# ant_esc_schematic.net
KiCad netlist of a schematic drawn in EAGLE
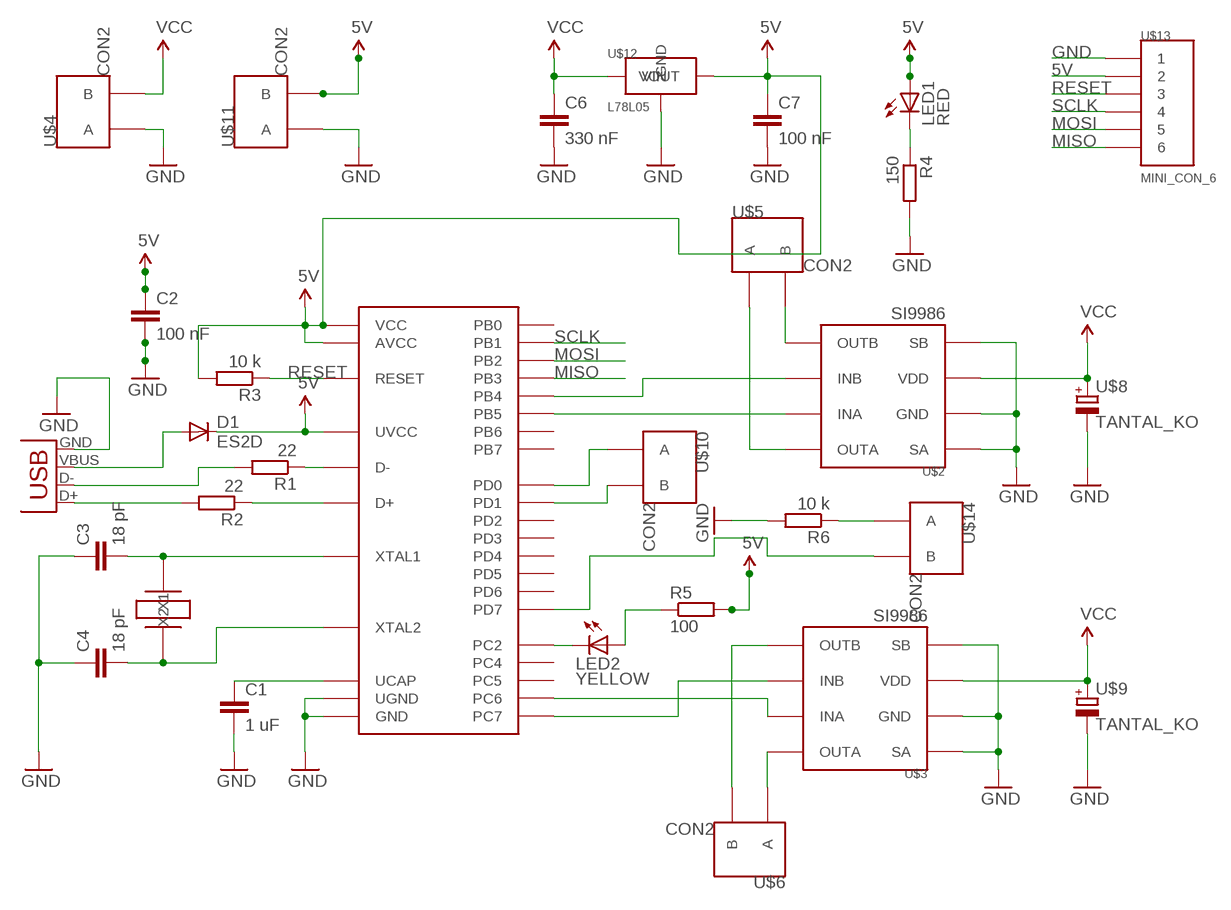
[diagram p0: schematic, sheet 1]

(export (version "E")
  (design (tool "Eeschema 10.0.6"))
  (components
    (comp (ref "C1")
      (value "1 uF")
      (footprint "eagle-import:C0805")
      (libsource (lib "eagle-import") (part "C-EUC0805"))
    )
    (comp (ref "C2")
      (value "100 nF")
      (footprint "eagle-import:C0805")
      (libsource (lib "eagle-import") (part "C-EUC0805"))
    )
    (comp (ref "C3")
      (value "18 pF")
      (footprint "eagle-import:C0805")
      (libsource (lib "eagle-import") (part "C-EUC0805"))
    )
    (comp (ref "C4")
      (value "18 pF")
      (footprint "eagle-import:C0805")
      (libsource (lib "eagle-import") (part "C-EUC0805"))
    )
    (comp (ref "C6")
      (value "330 nF")
      (footprint "eagle-import:C0805")
      (libsource (lib "eagle-import") (part "C-EUC0805"))
    )
    (comp (ref "C7")
      (value "100 nF")
      (footprint "eagle-import:C0805")
      (libsource (lib "eagle-import") (part "C-EUC0805"))
    )
    (comp (ref "D1")
      (value "ES2D")
      (footprint "eagle-import:SMB")
      (libsource (lib "eagle-import") (part "ES2D"))
    )
    (comp (ref "JP1")
      (value "USBSMD")
      (footprint "eagle-import:USB-MINIB")
      (libsource (lib "eagle-import") (part "USBSMD"))
    )
    (comp (ref "LED1")
      (value "RED")
      (footprint "eagle-import:CHIPLED_0805")
      (libsource (lib "eagle-import") (part "LEDCHIPLED_0805"))
    )
    (comp (ref "LED2")
      (value "YELLOW")
      (footprint "eagle-import:CHIPLED_0805")
      (libsource (lib "eagle-import") (part "LEDCHIPLED_0805"))
    )
    (comp (ref "R1")
      (value "22")
      (footprint "eagle-import:M0805")
      (libsource (lib "eagle-import") (part "R-EU_M0805"))
    )
    (comp (ref "R2")
      (value "22")
      (footprint "eagle-import:M0805")
      (libsource (lib "eagle-import") (part "R-EU_M0805"))
    )
    (comp (ref "R3")
      (value "10 k")
      (footprint "eagle-import:M0805")
      (libsource (lib "eagle-import") (part "R-EU_M0805"))
    )
    (comp (ref "R4")
      (value "150")
      (footprint "eagle-import:M0805")
      (libsource (lib "eagle-import") (part "R-EU_M0805"))
    )
    (comp (ref "R5")
      (value "100")
      (footprint "eagle-import:M0805")
      (libsource (lib "eagle-import") (part "R-EU_M0805"))
    )
    (comp (ref "R6")
      (value "10 k")
      (footprint "eagle-import:M0805")
      (libsource (lib "eagle-import") (part "R-EU_M0805"))
    )
    (comp (ref "U$1")
      (value "ATMEGA8U2")
      (footprint "eagle-import:TQFP32-08")
      (libsource (lib "eagle-import") (part "ATMEGA8U2"))
    )
    (comp (ref "U$2")
      (value "SI9986")
      (footprint "eagle-import:SOIC8")
      (libsource (lib "eagle-import") (part "SI9986"))
    )
    (comp (ref "U$3")
      (value "SI9986")
      (footprint "eagle-import:SOIC8")
      (libsource (lib "eagle-import") (part "SI9986"))
    )
    (comp (ref "U$4")
      (value "CON2")
      (footprint "eagle-import:332-02")
      (libsource (lib "eagle-import") (part "CON2"))
    )
    (comp (ref "U$5")
      (value "CON2")
      (footprint "eagle-import:332-02")
      (libsource (lib "eagle-import") (part "CON2"))
    )
    (comp (ref "U$6")
      (value "CON2")
      (footprint "eagle-import:332-02")
      (libsource (lib "eagle-import") (part "CON2"))
    )
    (comp (ref "U$7")
      (value "16 MHz")
      (footprint "eagle-import:ABM3")
      (libsource (lib "eagle-import") (part "XTAL_16MHZ_ABM3"))
    )
    (comp (ref "U$8")
      (value "TANTAL_KO")
      (footprint "eagle-import:KEMET_C")
      (libsource (lib "eagle-import") (part "TANTAL_KO"))
    )
    (comp (ref "U$9")
      (value "TANTAL_KO")
      (footprint "eagle-import:KEMET_C")
      (libsource (lib "eagle-import") (part "TANTAL_KO"))
    )
    (comp (ref "U$10")
      (value "CON2")
      (footprint "eagle-import:332-02")
      (libsource (lib "eagle-import") (part "CON2"))
    )
    (comp (ref "U$11")
      (value "CON2")
      (footprint "eagle-import:332-02")
      (libsource (lib "eagle-import") (part "CON2"))
    )
    (comp (ref "U$12")
      (value "L78L05")
      (footprint "eagle-import:SOT89")
      (libsource (lib "eagle-import") (part "L78L05"))
    )
    (comp (ref "U$13")
      (value "MINI_CON_6")
      (footprint "eagle-import:MIN_CON_6")
      (libsource (lib "eagle-import") (part "MINI_CON_6"))
    )
    (comp (ref "U$14")
      (value "CON2")
      (footprint "eagle-import:332-02")
      (libsource (lib "eagle-import") (part "CON2"))
    )
  )
  (nets
    (net (code "1") (name "/MISO") (class "Default")
      (node (ref "U$1") (pin "PB3") (pinfunction "PB3_PB3") (pintype "bidirectional"))
      (node (ref "U$13") (pin "6") (pinfunction "6_6") (pintype "bidirectional"))
    )
    (net (code "2") (name "/MOSI") (class "Default")
      (node (ref "U$1") (pin "PB2") (pinfunction "PB2_PB2") (pintype "bidirectional"))
      (node (ref "U$13") (pin "5") (pinfunction "5_5") (pintype "bidirectional"))
    )
    (net (code "3") (name "/RESET") (class "Default")
      (node (ref "R3") (pin "1") (pinfunction "1_1") (pintype "passive"))
      (node (ref "U$1") (pin "RESET") (pinfunction "RESET_RESET") (pintype "bidirectional"))
      (node (ref "U$13") (pin "3") (pinfunction "3_3") (pintype "bidirectional"))
    )
    (net (code "4") (name "/SCLK") (class "Default")
      (node (ref "U$1") (pin "PB1") (pinfunction "PB1_PB1") (pintype "bidirectional"))
      (node (ref "U$13") (pin "4") (pinfunction "4_4") (pintype "bidirectional"))
    )
    (net (code "5") (name "5V") (class "Default")
      (node (ref "C2") (pin "1") (pinfunction "1_1") (pintype "passive"))
      (node (ref "C7") (pin "1") (pinfunction "1_1") (pintype "passive"))
      (node (ref "D1") (pin "C") (pinfunction "C_C") (pintype "passive"))
      (node (ref "LED1") (pin "A") (pinfunction "A_A") (pintype "passive"))
      (node (ref "R3") (pin "2") (pinfunction "2_2") (pintype "passive"))
      (node (ref "R5") (pin "2") (pinfunction "2_2") (pintype "passive"))
      (node (ref "U$1") (pin "AVCC") (pinfunction "AVCC_AVCC") (pintype "bidirectional"))
      (node (ref "U$1") (pin "UVCC") (pinfunction "UVCC_UVCC") (pintype "bidirectional"))
      (node (ref "U$1") (pin "VCC") (pinfunction "VCC_VCC") (pintype "bidirectional"))
      (node (ref "U$11") (pin "2") (pinfunction "B_2") (pintype "bidirectional"))
      (node (ref "U$12") (pin "VOUT") (pinfunction "VOUT_VOUT") (pintype "bidirectional"))
      (node (ref "U$13") (pin "2") (pinfunction "2_2") (pintype "bidirectional"))
    )
    (net (code "6") (name "GND") (class "Default")
      (node (ref "C1") (pin "2") (pinfunction "2_2") (pintype "passive"))
      (node (ref "C2") (pin "2") (pinfunction "2_2") (pintype "passive"))
      (node (ref "C3") (pin "1") (pinfunction "1_1") (pintype "passive"))
      (node (ref "C4") (pin "1") (pinfunction "1_1") (pintype "passive"))
      (node (ref "C6") (pin "2") (pinfunction "2_2") (pintype "passive"))
      (node (ref "C7") (pin "2") (pinfunction "2_2") (pintype "passive"))
      (node (ref "JP1") (pin "GND") (pinfunction "GND_GND") (pintype "bidirectional"))
      (node (ref "R4") (pin "2") (pinfunction "2_2") (pintype "passive"))
      (node (ref "R6") (pin "2") (pinfunction "2_2") (pintype "passive"))
      (node (ref "U$1") (pin "GND") (pinfunction "GND_GND") (pintype "bidirectional"))
      (node (ref "U$1") (pin "UGND") (pinfunction "UGND_UGND") (pintype "bidirectional"))
      (node (ref "U$11") (pin "1") (pinfunction "A_1") (pintype "bidirectional"))
      (node (ref "U$12") (pin "2@1") (pinfunction "GND_2@1") (pintype "bidirectional"))
      (node (ref "U$12") (pin "GND") (pinfunction "GND_GND") (pintype "bidirectional"))
      (node (ref "U$13") (pin "1") (pinfunction "1_1") (pintype "bidirectional"))
      (node (ref "U$2") (pin "GND") (pinfunction "GND_GND") (pintype "bidirectional"))
      (node (ref "U$2") (pin "SA") (pinfunction "SA_SA") (pintype "bidirectional"))
      (node (ref "U$2") (pin "SB") (pinfunction "SB_SB") (pintype "bidirectional"))
      (node (ref "U$3") (pin "GND") (pinfunction "GND_GND") (pintype "bidirectional"))
      (node (ref "U$3") (pin "SA") (pinfunction "SA_SA") (pintype "bidirectional"))
      (node (ref "U$3") (pin "SB") (pinfunction "SB_SB") (pintype "bidirectional"))
      (node (ref "U$4") (pin "1") (pinfunction "A_1") (pintype "bidirectional"))
      (node (ref "U$8") (pin "CATHODE-") (pinfunction "-_CATHODE-") (pintype "passive"))
      (node (ref "U$9") (pin "CATHODE-") (pinfunction "-_CATHODE-") (pintype "passive"))
    )
    (net (code "7") (name "Net-(C1-Pad1)") (class "Default")
      (node (ref "C1") (pin "1") (pinfunction "1_1") (pintype "passive"))
      (node (ref "U$1") (pin "UCAP") (pinfunction "UCAP_UCAP") (pintype "bidirectional"))
    )
    (net (code "8") (name "Net-(C3-Pad2)") (class "Default")
      (node (ref "C3") (pin "2") (pinfunction "2_2") (pintype "passive"))
      (node (ref "U$1") (pin "XTAL1") (pinfunction "XTAL1_XTAL1") (pintype "bidirectional"))
      (node (ref "U$7") (pin "X2") (pinfunction "X2_X2") (pintype "bidirectional"))
    )
    (net (code "9") (name "Net-(C4-Pad2)") (class "Default")
      (node (ref "C4") (pin "2") (pinfunction "2_2") (pintype "passive"))
      (node (ref "U$1") (pin "XTAL2") (pinfunction "XTAL2_XTAL2") (pintype "bidirectional"))
      (node (ref "U$7") (pin "X1") (pinfunction "X1_X1") (pintype "bidirectional"))
    )
    (net (code "10") (name "Net-(D1-PadA)") (class "Default")
      (node (ref "D1") (pin "A") (pinfunction "A_A") (pintype "passive"))
      (node (ref "JP1") (pin "VBUS") (pinfunction "VBUS_VBUS") (pintype "bidirectional"))
    )
    (net (code "11") (name "Net-(JP1-PadD+)") (class "Default")
      (node (ref "JP1") (pin "D+") (pinfunction "D+_D+") (pintype "bidirectional"))
      (node (ref "R2") (pin "2") (pinfunction "2_2") (pintype "passive"))
    )
    (net (code "12") (name "Net-(JP1-PadD-)") (class "Default")
      (node (ref "JP1") (pin "D-") (pinfunction "D-_D-") (pintype "bidirectional"))
      (node (ref "R1") (pin "2") (pinfunction "2_2") (pintype "passive"))
    )
    (net (code "13") (name "Net-(LED1-PadC)") (class "Default")
      (node (ref "LED1") (pin "C") (pinfunction "C_C") (pintype "passive"))
      (node (ref "R4") (pin "1") (pinfunction "1_1") (pintype "passive"))
    )
    (net (code "14") (name "Net-(LED2-PadA)") (class "Default")
      (node (ref "LED2") (pin "A") (pinfunction "A_A") (pintype "passive"))
      (node (ref "R5") (pin "1") (pinfunction "1_1") (pintype "passive"))
    )
    (net (code "15") (name "Net-(LED2-PadC)") (class "Default")
      (node (ref "LED2") (pin "C") (pinfunction "C_C") (pintype "passive"))
      (node (ref "U$1") (pin "PC2") (pinfunction "PC2_PC2") (pintype "bidirectional"))
    )
    (net (code "16") (name "Net-(R1-Pad1)") (class "Default")
      (node (ref "R1") (pin "1") (pinfunction "1_1") (pintype "passive"))
      (node (ref "U$1") (pin "D-") (pinfunction "D-_D-") (pintype "bidirectional"))
    )
    (net (code "17") (name "Net-(R2-Pad1)") (class "Default")
      (node (ref "R2") (pin "1") (pinfunction "1_1") (pintype "passive"))
      (node (ref "U$1") (pin "D+") (pinfunction "D+_D+") (pintype "bidirectional"))
    )
    (net (code "18") (name "Net-(U$1-PadPB4)") (class "Default")
      (node (ref "U$1") (pin "PB4") (pinfunction "PB4_PB4") (pintype "bidirectional"))
      (node (ref "U$2") (pin "INB") (pinfunction "INB_INB") (pintype "bidirectional"))
    )
    (net (code "19") (name "Net-(U$1-PadPB5)") (class "Default")
      (node (ref "U$1") (pin "PB5") (pinfunction "PB5_PB5") (pintype "bidirectional"))
      (node (ref "U$2") (pin "INA") (pinfunction "INA_INA") (pintype "bidirectional"))
    )
    (net (code "20") (name "Net-(U$1-PadPC6)") (class "Default")
      (node (ref "U$1") (pin "PC6") (pinfunction "PC6_PC6") (pintype "bidirectional"))
      (node (ref "U$3") (pin "INA") (pinfunction "INA_INA") (pintype "bidirectional"))
    )
    (net (code "21") (name "Net-(U$1-PadPC7)") (class "Default")
      (node (ref "U$1") (pin "PC7") (pinfunction "PC7_PC7") (pintype "bidirectional"))
      (node (ref "U$3") (pin "INB") (pinfunction "INB_INB") (pintype "bidirectional"))
    )
    (net (code "22") (name "Net-(U$5-A)") (class "Default")
      (node (ref "U$2") (pin "OUTA") (pinfunction "OUTA_OUTA") (pintype "bidirectional"))
      (node (ref "U$5") (pin "1") (pinfunction "A_1") (pintype "bidirectional"))
    )
    (net (code "23") (name "Net-(U$5-B)") (class "Default")
      (node (ref "U$2") (pin "OUTB") (pinfunction "OUTB_OUTB") (pintype "bidirectional"))
      (node (ref "U$5") (pin "2") (pinfunction "B_2") (pintype "bidirectional"))
    )
    (net (code "24") (name "Net-(U$6-A)") (class "Default")
      (node (ref "U$3") (pin "OUTA") (pinfunction "OUTA_OUTA") (pintype "bidirectional"))
      (node (ref "U$6") (pin "1") (pinfunction "A_1") (pintype "bidirectional"))
    )
    (net (code "25") (name "Net-(U$6-B)") (class "Default")
      (node (ref "U$3") (pin "OUTB") (pinfunction "OUTB_OUTB") (pintype "bidirectional"))
      (node (ref "U$6") (pin "2") (pinfunction "B_2") (pintype "bidirectional"))
    )
    (net (code "26") (name "Net-(U$10-A)") (class "Default")
      (node (ref "U$1") (pin "PD0") (pinfunction "PD0_PD0") (pintype "bidirectional"))
      (node (ref "U$10") (pin "1") (pinfunction "A_1") (pintype "bidirectional"))
    )
    (net (code "27") (name "Net-(U$10-B)") (class "Default")
      (node (ref "U$1") (pin "PD1") (pinfunction "PD1_PD1") (pintype "bidirectional"))
      (node (ref "U$10") (pin "2") (pinfunction "B_2") (pintype "bidirectional"))
    )
    (net (code "28") (name "Net-(U$14-A)") (class "Default")
      (node (ref "R6") (pin "1") (pinfunction "1_1") (pintype "passive"))
      (node (ref "U$14") (pin "1") (pinfunction "A_1") (pintype "bidirectional"))
    )
    (net (code "29") (name "Net-(U$14-B)") (class "Default")
      (node (ref "U$1") (pin "PD7") (pinfunction "PD7_PD7") (pintype "bidirectional"))
      (node (ref "U$14") (pin "2") (pinfunction "B_2") (pintype "bidirectional"))
    )
    (net (code "30") (name "VCC") (class "Default")
      (node (ref "C6") (pin "1") (pinfunction "1_1") (pintype "passive"))
      (node (ref "U$12") (pin "VIN") (pinfunction "VIN_VIN") (pintype "bidirectional"))
      (node (ref "U$2") (pin "VDD") (pinfunction "VDD_VDD") (pintype "bidirectional"))
      (node (ref "U$3") (pin "VDD") (pinfunction "VDD_VDD") (pintype "bidirectional"))
      (node (ref "U$4") (pin "2") (pinfunction "B_2") (pintype "bidirectional"))
      (node (ref "U$8") (pin "ANODE+") (pinfunction "+_ANODE+") (pintype "passive"))
      (node (ref "U$9") (pin "ANODE+") (pinfunction "+_ANODE+") (pintype "passive"))
    )
    (net (code "31") (name "unconnected-(U$1-PadPB0)") (class "Default")
      (node (ref "U$1") (pin "PB0") (pinfunction "PB0_PB0") (pintype "bidirectional"))
    )
    (net (code "32") (name "unconnected-(U$1-PadPB6)") (class "Default")
      (node (ref "U$1") (pin "PB6") (pinfunction "PB6_PB6") (pintype "bidirectional"))
    )
    (net (code "33") (name "unconnected-(U$1-PadPB7)") (class "Default")
      (node (ref "U$1") (pin "PB7") (pinfunction "PB7_PB7") (pintype "bidirectional"))
    )
    (net (code "34") (name "unconnected-(U$1-PadPC4)") (class "Default")
      (node (ref "U$1") (pin "PC4") (pinfunction "PC4_PC4") (pintype "bidirectional"))
    )
    (net (code "35") (name "unconnected-(U$1-PadPC5)") (class "Default")
      (node (ref "U$1") (pin "PC5") (pinfunction "PC5_PC5") (pintype "bidirectional"))
    )
    (net (code "36") (name "unconnected-(U$1-PadPD2)") (class "Default")
      (node (ref "U$1") (pin "PD2") (pinfunction "PD2_PD2") (pintype "bidirectional"))
    )
    (net (code "37") (name "unconnected-(U$1-PadPD3)") (class "Default")
      (node (ref "U$1") (pin "PD3") (pinfunction "PD3_PD3") (pintype "bidirectional"))
    )
    (net (code "38") (name "unconnected-(U$1-PadPD4)") (class "Default")
      (node (ref "U$1") (pin "PD4") (pinfunction "PD4_PD4") (pintype "bidirectional"))
    )
    (net (code "39") (name "unconnected-(U$1-PadPD5)") (class "Default")
      (node (ref "U$1") (pin "PD5") (pinfunction "PD5_PD5") (pintype "bidirectional"))
    )
    (net (code "40") (name "unconnected-(U$1-PadPD6)") (class "Default")
      (node (ref "U$1") (pin "PD6") (pinfunction "PD6_PD6") (pintype "bidirectional"))
    )
  )
)
